# 03_RFID.net
KiCad netlist of a schematic drawn in Altium Designer
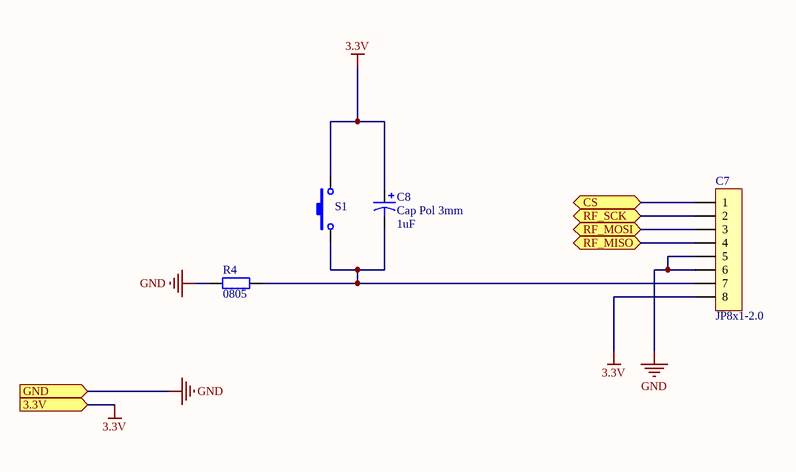
[diagram p0: 03_RFID.SchDoc]

(export (version "E")
  (design (tool "Eeschema 10.0.6"))
  (components
    (comp (ref "C7")
      (value "JP8x1-2.0")
      (footprint "J8-C1T")
      (description "WR-PHD 2.00 mm Socket Header")
      (fields
        (field (name "MANUFACTURER") "Würth Elektronik eiSos GmbH")
        (field (name "PARTNO") "62000811821")
        (field (name "CREATED BY") "Karrer Zheng")
      )
      (libsource (lib "My Library") (part "JP8x1-2.0"))
    )
    (comp (ref "C8")
      (value "Cap Pol 3mm")
      (footprint "C3MM")
      (description "Polarized Capacitor (Axial)")
      (fields (field (name "ALTIUM_UNNAMED_1") "1uF") (field (name "PUBLISHER") "Altium Limited"))
      (libsource (lib "My Library") (part "Cap Pol 3mm"))
    )
    (comp (ref "R4")
      (value "0805")
      (footprint "DIEN TRO 0805")
      (description "Resistor SMD 0805")
      (fields (field (name "Comment") "R0805") (field (name "PUBLISHER") "Altium Limited"))
      (libsource (lib "My Library") (part "R0805"))
    )
    (comp (ref "S1")
      (value "SW-SMD")
      (footprint "SW-SMD")
      (description "Switch")
      (fields (field (name "PUBLISHER") "Altium Limited"))
      (libsource (lib "My Library") (part "SW-SMD"))
    )
  )
  (nets
    (net (code "1") (name "/CS") (class "Default")
      (node (ref "C7") (pin "1") (pinfunction "1_1") (pintype "passive"))
    )
    (net (code "2") (name "/RF_MISO") (class "Default")
      (node (ref "C7") (pin "4") (pinfunction "4_4") (pintype "passive"))
    )
    (net (code "3") (name "/RF_MOSI") (class "Default")
      (node (ref "C7") (pin "3") (pinfunction "3_3") (pintype "passive"))
    )
    (net (code "4") (name "/RF_SCK") (class "Default")
      (node (ref "C7") (pin "2") (pinfunction "2_2") (pintype "passive"))
    )
    (net (code "5") (name "3.3V") (class "Default")
      (node (ref "C7") (pin "8") (pinfunction "8_8") (pintype "passive"))
      (node (ref "C8") (pin "1") (pinfunction "1_1") (pintype "passive"))
      (node (ref "S1") (pin "2") (pinfunction "2_2") (pintype "passive"))
    )
    (net (code "6") (name "GND") (class "Default")
      (node (ref "C7") (pin "5") (pinfunction "5_5") (pintype "passive"))
      (node (ref "C7") (pin "6") (pinfunction "6_6") (pintype "passive"))
      (node (ref "R4") (pin "1") (pinfunction "1_1") (pintype "passive"))
    )
    (net (code "7") (name "Net-(C7-Pad7)") (class "Default")
      (node (ref "C7") (pin "7") (pinfunction "7_7") (pintype "passive"))
      (node (ref "C8") (pin "2") (pinfunction "2_2") (pintype "passive"))
      (node (ref "R4") (pin "2") (pinfunction "2_2") (pintype "passive"))
      (node (ref "S1") (pin "1") (pinfunction "1_1") (pintype "passive"))
    )
  )
)
